# Symbs.net
KiCad netlist of a schematic drawn in Altium Designer
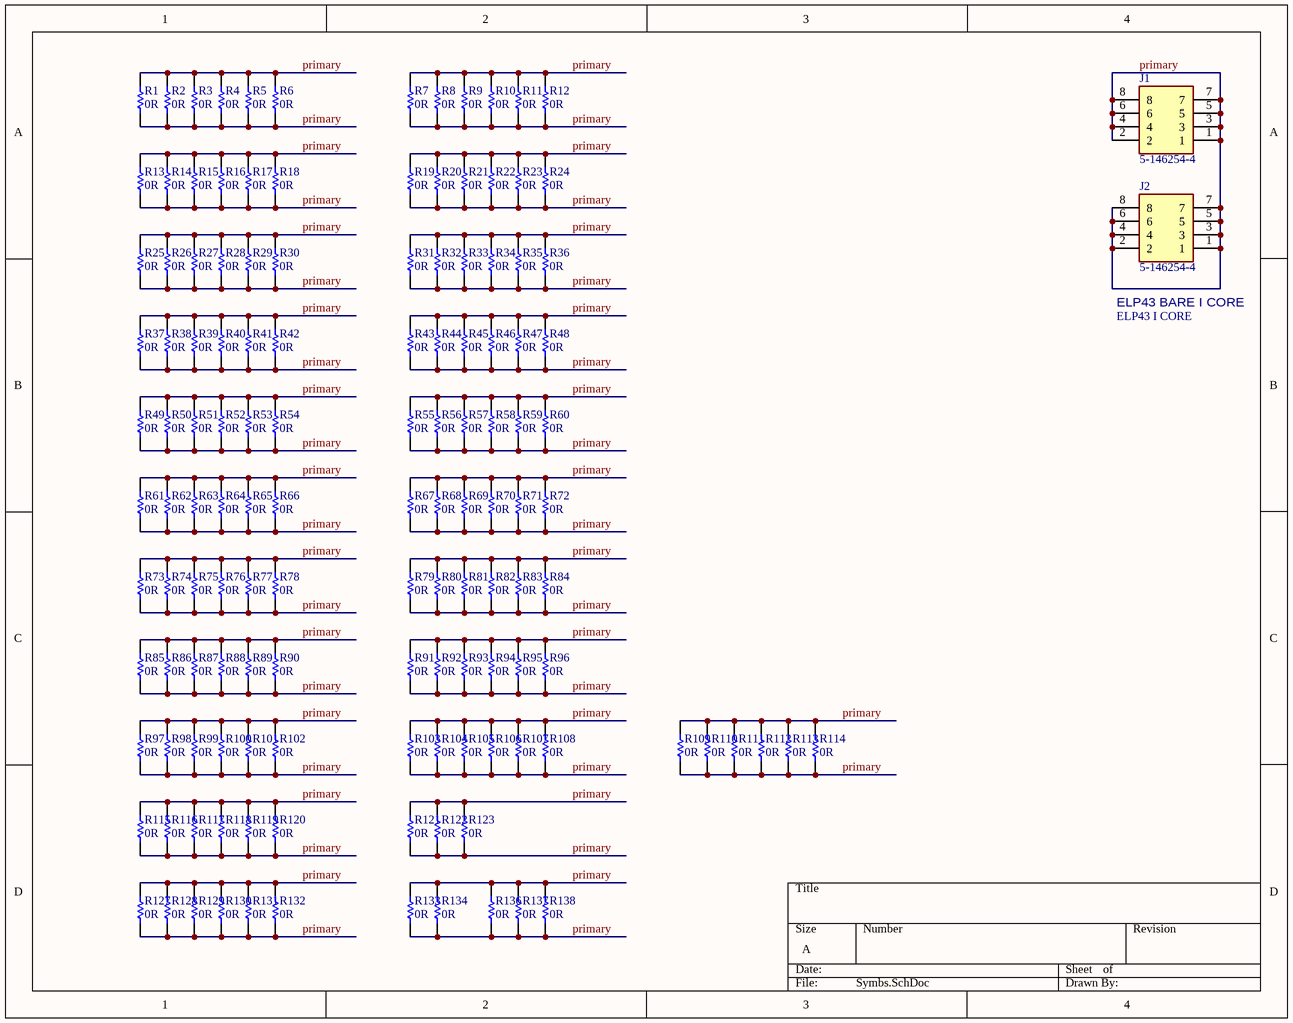
[diagram p0: Symbs.SchDoc]

(export (version "E")
  (design (tool "Eeschema 10.0.6"))
  (components
    (comp (ref "BODIES1")
      (value "ELP43 I CORE")
      (footprint "B66291G0000X187")
      (description "BODIES - ELP43 3D BODY CORE, I CORE")
      (libsource (lib "SamacSys") (part "ELP43 I CORE"))
    )
    (comp (ref "J1")
      (value "5-146254-4")
      (footprint "SamacSys:51462544")
      (description "Connector")
      (fields (field (name "MOUSER PART NUMBER") "571-5-146254-4"))
      (libsource (lib "*") (part "5-146254-4"))
    )
    (comp (ref "J2")
      (value "5-146254-4")
      (footprint "SamacSys:51462544")
      (description "Connector")
      (fields (field (name "MOUSER PART NUMBER") "571-5-146254-4"))
      (libsource (lib "*") (part "5-146254-4"))
    )
    (comp (ref "R1")
      (value "0R")
      (footprint "R_1206")
      (description "R - RESISTOR - SMD - 0R - 1% - 1206")
      (fields (field (name "LCSC PART #") "C17888") (field (name "Comment") "1206W4F0000T5E"))
      (libsource (lib "JLC_PCB") (part "1206W4F0000T5E"))
    )
    (comp (ref "R2")
      (value "0R")
      (footprint "R_1206")
      (description "R - RESISTOR - SMD - 0R - 1% - 1206")
      (fields (field (name "LCSC PART #") "C17888") (field (name "Comment") "1206W4F0000T5E"))
      (libsource (lib "JLC_PCB") (part "1206W4F0000T5E"))
    )
    (comp (ref "R3")
      (value "0R")
      (footprint "R_1206")
      (description "R - RESISTOR - SMD - 0R - 1% - 1206")
      (fields (field (name "LCSC PART #") "C17888") (field (name "Comment") "1206W4F0000T5E"))
      (libsource (lib "JLC_PCB") (part "1206W4F0000T5E"))
    )
    (comp (ref "R4")
      (value "0R")
      (footprint "R_1206")
      (description "R - RESISTOR - SMD - 0R - 1% - 1206")
      (fields (field (name "LCSC PART #") "C17888") (field (name "Comment") "1206W4F0000T5E"))
      (libsource (lib "JLC_PCB") (part "1206W4F0000T5E"))
    )
    (comp (ref "R5")
      (value "0R")
      (footprint "R_1206")
      (description "R - RESISTOR - SMD - 0R - 1% - 1206")
      (fields (field (name "LCSC PART #") "C17888") (field (name "Comment") "1206W4F0000T5E"))
      (libsource (lib "JLC_PCB") (part "1206W4F0000T5E"))
    )
    (comp (ref "R6")
      (value "0R")
      (footprint "R_1206")
      (description "R - RESISTOR - SMD - 0R - 1% - 1206")
      (fields (field (name "LCSC PART #") "C17888") (field (name "Comment") "1206W4F0000T5E"))
      (libsource (lib "JLC_PCB") (part "1206W4F0000T5E"))
    )
    (comp (ref "R7")
      (value "0R")
      (footprint "R_1206")
      (description "R - RESISTOR - SMD - 0R - 1% - 1206")
      (fields (field (name "LCSC PART #") "C17888") (field (name "Comment") "1206W4F0000T5E"))
      (libsource (lib "JLC_PCB") (part "1206W4F0000T5E"))
    )
    (comp (ref "R8")
      (value "0R")
      (footprint "R_1206")
      (description "R - RESISTOR - SMD - 0R - 1% - 1206")
      (fields (field (name "LCSC PART #") "C17888") (field (name "Comment") "1206W4F0000T5E"))
      (libsource (lib "JLC_PCB") (part "1206W4F0000T5E"))
    )
    (comp (ref "R9")
      (value "0R")
      (footprint "R_1206")
      (description "R - RESISTOR - SMD - 0R - 1% - 1206")
      (fields (field (name "LCSC PART #") "C17888") (field (name "Comment") "1206W4F0000T5E"))
      (libsource (lib "JLC_PCB") (part "1206W4F0000T5E"))
    )
    (comp (ref "R10")
      (value "0R")
      (footprint "R_1206")
      (description "R - RESISTOR - SMD - 0R - 1% - 1206")
      (fields (field (name "LCSC PART #") "C17888") (field (name "Comment") "1206W4F0000T5E"))
      (libsource (lib "JLC_PCB") (part "1206W4F0000T5E"))
    )
    (comp (ref "R11")
      (value "0R")
      (footprint "R_1206")
      (description "R - RESISTOR - SMD - 0R - 1% - 1206")
      (fields (field (name "LCSC PART #") "C17888") (field (name "Comment") "1206W4F0000T5E"))
      (libsource (lib "JLC_PCB") (part "1206W4F0000T5E"))
    )
    (comp (ref "R12")
      (value "0R")
      (footprint "R_1206")
      (description "R - RESISTOR - SMD - 0R - 1% - 1206")
      (fields (field (name "LCSC PART #") "C17888") (field (name "Comment") "1206W4F0000T5E"))
      (libsource (lib "JLC_PCB") (part "1206W4F0000T5E"))
    )
    (comp (ref "R13")
      (value "0R")
      (footprint "R_1206")
      (description "R - RESISTOR - SMD - 0R - 1% - 1206")
      (fields (field (name "LCSC PART #") "C17888") (field (name "Comment") "1206W4F0000T5E"))
      (libsource (lib "JLC_PCB") (part "1206W4F0000T5E"))
    )
    (comp (ref "R14")
      (value "0R")
      (footprint "R_1206")
      (description "R - RESISTOR - SMD - 0R - 1% - 1206")
      (fields (field (name "LCSC PART #") "C17888") (field (name "Comment") "1206W4F0000T5E"))
      (libsource (lib "JLC_PCB") (part "1206W4F0000T5E"))
    )
    (comp (ref "R15")
      (value "0R")
      (footprint "R_1206")
      (description "R - RESISTOR - SMD - 0R - 1% - 1206")
      (fields (field (name "LCSC PART #") "C17888") (field (name "Comment") "1206W4F0000T5E"))
      (libsource (lib "JLC_PCB") (part "1206W4F0000T5E"))
    )
    (comp (ref "R16")
      (value "0R")
      (footprint "R_1206")
      (description "R - RESISTOR - SMD - 0R - 1% - 1206")
      (fields (field (name "LCSC PART #") "C17888") (field (name "Comment") "1206W4F0000T5E"))
      (libsource (lib "JLC_PCB") (part "1206W4F0000T5E"))
    )
    (comp (ref "R17")
      (value "0R")
      (footprint "R_1206")
      (description "R - RESISTOR - SMD - 0R - 1% - 1206")
      (fields (field (name "LCSC PART #") "C17888") (field (name "Comment") "1206W4F0000T5E"))
      (libsource (lib "JLC_PCB") (part "1206W4F0000T5E"))
    )
    (comp (ref "R18")
      (value "0R")
      (footprint "R_1206")
      (description "R - RESISTOR - SMD - 0R - 1% - 1206")
      (fields (field (name "LCSC PART #") "C17888") (field (name "Comment") "1206W4F0000T5E"))
      (libsource (lib "JLC_PCB") (part "1206W4F0000T5E"))
    )
    (comp (ref "R19")
      (value "0R")
      (footprint "R_1206")
      (description "R - RESISTOR - SMD - 0R - 1% - 1206")
      (fields (field (name "LCSC PART #") "C17888") (field (name "Comment") "1206W4F0000T5E"))
      (libsource (lib "JLC_PCB") (part "1206W4F0000T5E"))
    )
    (comp (ref "R20")
      (value "0R")
      (footprint "R_1206")
      (description "R - RESISTOR - SMD - 0R - 1% - 1206")
      (fields (field (name "LCSC PART #") "C17888") (field (name "Comment") "1206W4F0000T5E"))
      (libsource (lib "JLC_PCB") (part "1206W4F0000T5E"))
    )
    (comp (ref "R21")
      (value "0R")
      (footprint "R_1206")
      (description "R - RESISTOR - SMD - 0R - 1% - 1206")
      (fields (field (name "LCSC PART #") "C17888") (field (name "Comment") "1206W4F0000T5E"))
      (libsource (lib "JLC_PCB") (part "1206W4F0000T5E"))
    )
    (comp (ref "R22")
      (value "0R")
      (footprint "R_1206")
      (description "R - RESISTOR - SMD - 0R - 1% - 1206")
      (fields (field (name "LCSC PART #") "C17888") (field (name "Comment") "1206W4F0000T5E"))
      (libsource (lib "JLC_PCB") (part "1206W4F0000T5E"))
    )
    (comp (ref "R23")
      (value "0R")
      (footprint "R_1206")
      (description "R - RESISTOR - SMD - 0R - 1% - 1206")
      (fields (field (name "LCSC PART #") "C17888") (field (name "Comment") "1206W4F0000T5E"))
      (libsource (lib "JLC_PCB") (part "1206W4F0000T5E"))
    )
    (comp (ref "R24")
      (value "0R")
      (footprint "R_1206")
      (description "R - RESISTOR - SMD - 0R - 1% - 1206")
      (fields (field (name "LCSC PART #") "C17888") (field (name "Comment") "1206W4F0000T5E"))
      (libsource (lib "JLC_PCB") (part "1206W4F0000T5E"))
    )
    (comp (ref "R25")
      (value "0R")
      (footprint "R_1206")
      (description "R - RESISTOR - SMD - 0R - 1% - 1206")
      (fields (field (name "LCSC PART #") "C17888") (field (name "Comment") "1206W4F0000T5E"))
      (libsource (lib "JLC_PCB") (part "1206W4F0000T5E"))
    )
    (comp (ref "R26")
      (value "0R")
      (footprint "R_1206")
      (description "R - RESISTOR - SMD - 0R - 1% - 1206")
      (fields (field (name "LCSC PART #") "C17888") (field (name "Comment") "1206W4F0000T5E"))
      (libsource (lib "JLC_PCB") (part "1206W4F0000T5E"))
    )
    (comp (ref "R27")
      (value "0R")
      (footprint "R_1206")
      (description "R - RESISTOR - SMD - 0R - 1% - 1206")
      (fields (field (name "LCSC PART #") "C17888") (field (name "Comment") "1206W4F0000T5E"))
      (libsource (lib "JLC_PCB") (part "1206W4F0000T5E"))
    )
    (comp (ref "R28")
      (value "0R")
      (footprint "R_1206")
      (description "R - RESISTOR - SMD - 0R - 1% - 1206")
      (fields (field (name "LCSC PART #") "C17888") (field (name "Comment") "1206W4F0000T5E"))
      (libsource (lib "JLC_PCB") (part "1206W4F0000T5E"))
    )
    (comp (ref "R29")
      (value "0R")
      (footprint "R_1206")
      (description "R - RESISTOR - SMD - 0R - 1% - 1206")
      (fields (field (name "LCSC PART #") "C17888") (field (name "Comment") "1206W4F0000T5E"))
      (libsource (lib "JLC_PCB") (part "1206W4F0000T5E"))
    )
    (comp (ref "R30")
      (value "0R")
      (footprint "R_1206")
      (description "R - RESISTOR - SMD - 0R - 1% - 1206")
      (fields (field (name "LCSC PART #") "C17888") (field (name "Comment") "1206W4F0000T5E"))
      (libsource (lib "JLC_PCB") (part "1206W4F0000T5E"))
    )
    (comp (ref "R31")
      (value "0R")
      (footprint "R_1206")
      (description "R - RESISTOR - SMD - 0R - 1% - 1206")
      (fields (field (name "LCSC PART #") "C17888") (field (name "Comment") "1206W4F0000T5E"))
      (libsource (lib "JLC_PCB") (part "1206W4F0000T5E"))
    )
    (comp (ref "R32")
      (value "0R")
      (footprint "R_1206")
      (description "R - RESISTOR - SMD - 0R - 1% - 1206")
      (fields (field (name "LCSC PART #") "C17888") (field (name "Comment") "1206W4F0000T5E"))
      (libsource (lib "JLC_PCB") (part "1206W4F0000T5E"))
    )
    (comp (ref "R33")
      (value "0R")
      (footprint "R_1206")
      (description "R - RESISTOR - SMD - 0R - 1% - 1206")
      (fields (field (name "LCSC PART #") "C17888") (field (name "Comment") "1206W4F0000T5E"))
      (libsource (lib "JLC_PCB") (part "1206W4F0000T5E"))
    )
    (comp (ref "R34")
      (value "0R")
      (footprint "R_1206")
      (description "R - RESISTOR - SMD - 0R - 1% - 1206")
      (fields (field (name "LCSC PART #") "C17888") (field (name "Comment") "1206W4F0000T5E"))
      (libsource (lib "JLC_PCB") (part "1206W4F0000T5E"))
    )
    (comp (ref "R35")
      (value "0R")
      (footprint "R_1206")
      (description "R - RESISTOR - SMD - 0R - 1% - 1206")
      (fields (field (name "LCSC PART #") "C17888") (field (name "Comment") "1206W4F0000T5E"))
      (libsource (lib "JLC_PCB") (part "1206W4F0000T5E"))
    )
    (comp (ref "R36")
      (value "0R")
      (footprint "R_1206")
      (description "R - RESISTOR - SMD - 0R - 1% - 1206")
      (fields (field (name "LCSC PART #") "C17888") (field (name "Comment") "1206W4F0000T5E"))
      (libsource (lib "JLC_PCB") (part "1206W4F0000T5E"))
    )
    (comp (ref "R37")
      (value "0R")
      (footprint "R_1206")
      (description "R - RESISTOR - SMD - 0R - 1% - 1206")
      (fields (field (name "LCSC PART #") "C17888") (field (name "Comment") "1206W4F0000T5E"))
      (libsource (lib "JLC_PCB") (part "1206W4F0000T5E"))
    )
    (comp (ref "R38")
      (value "0R")
      (footprint "R_1206")
      (description "R - RESISTOR - SMD - 0R - 1% - 1206")
      (fields (field (name "LCSC PART #") "C17888") (field (name "Comment") "1206W4F0000T5E"))
      (libsource (lib "JLC_PCB") (part "1206W4F0000T5E"))
    )
    (comp (ref "R39")
      (value "0R")
      (footprint "R_1206")
      (description "R - RESISTOR - SMD - 0R - 1% - 1206")
      (fields (field (name "LCSC PART #") "C17888") (field (name "Comment") "1206W4F0000T5E"))
      (libsource (lib "JLC_PCB") (part "1206W4F0000T5E"))
    )
    (comp (ref "R40")
      (value "0R")
      (footprint "R_1206")
      (description "R - RESISTOR - SMD - 0R - 1% - 1206")
      (fields (field (name "LCSC PART #") "C17888") (field (name "Comment") "1206W4F0000T5E"))
      (libsource (lib "JLC_PCB") (part "1206W4F0000T5E"))
    )
    (comp (ref "R41")
      (value "0R")
      (footprint "R_1206")
      (description "R - RESISTOR - SMD - 0R - 1% - 1206")
      (fields (field (name "LCSC PART #") "C17888") (field (name "Comment") "1206W4F0000T5E"))
      (libsource (lib "JLC_PCB") (part "1206W4F0000T5E"))
    )
    (comp (ref "R42")
      (value "0R")
      (footprint "R_1206")
      (description "R - RESISTOR - SMD - 0R - 1% - 1206")
      (fields (field (name "LCSC PART #") "C17888") (field (name "Comment") "1206W4F0000T5E"))
      (libsource (lib "JLC_PCB") (part "1206W4F0000T5E"))
    )
    (comp (ref "R43")
      (value "0R")
      (footprint "R_1206")
      (description "R - RESISTOR - SMD - 0R - 1% - 1206")
      (fields (field (name "LCSC PART #") "C17888") (field (name "Comment") "1206W4F0000T5E"))
      (libsource (lib "JLC_PCB") (part "1206W4F0000T5E"))
    )
    (comp (ref "R44")
      (value "0R")
      (footprint "R_1206")
      (description "R - RESISTOR - SMD - 0R - 1% - 1206")
      (fields (field (name "LCSC PART #") "C17888") (field (name "Comment") "1206W4F0000T5E"))
      (libsource (lib "JLC_PCB") (part "1206W4F0000T5E"))
    )
    (comp (ref "R45")
      (value "0R")
      (footprint "R_1206")
      (description "R - RESISTOR - SMD - 0R - 1% - 1206")
      (fields (field (name "LCSC PART #") "C17888") (field (name "Comment") "1206W4F0000T5E"))
      (libsource (lib "JLC_PCB") (part "1206W4F0000T5E"))
    )
    (comp (ref "R46")
      (value "0R")
      (footprint "R_1206")
      (description "R - RESISTOR - SMD - 0R - 1% - 1206")
      (fields (field (name "LCSC PART #") "C17888") (field (name "Comment") "1206W4F0000T5E"))
      (libsource (lib "JLC_PCB") (part "1206W4F0000T5E"))
    )
    (comp (ref "R47")
      (value "0R")
      (footprint "R_1206")
      (description "R - RESISTOR - SMD - 0R - 1% - 1206")
      (fields (field (name "LCSC PART #") "C17888") (field (name "Comment") "1206W4F0000T5E"))
      (libsource (lib "JLC_PCB") (part "1206W4F0000T5E"))
    )
    (comp (ref "R48")
      (value "0R")
      (footprint "R_1206")
      (description "R - RESISTOR - SMD - 0R - 1% - 1206")
      (fields (field (name "LCSC PART #") "C17888") (field (name "Comment") "1206W4F0000T5E"))
      (libsource (lib "JLC_PCB") (part "1206W4F0000T5E"))
    )
    (comp (ref "R49")
      (value "0R")
      (footprint "R_1206")
      (description "R - RESISTOR - SMD - 0R - 1% - 1206")
      (fields (field (name "LCSC PART #") "C17888") (field (name "Comment") "1206W4F0000T5E"))
      (libsource (lib "JLC_PCB") (part "1206W4F0000T5E"))
    )
    (comp (ref "R50")
      (value "0R")
      (footprint "R_1206")
      (description "R - RESISTOR - SMD - 0R - 1% - 1206")
      (fields (field (name "LCSC PART #") "C17888") (field (name "Comment") "1206W4F0000T5E"))
      (libsource (lib "JLC_PCB") (part "1206W4F0000T5E"))
    )
    (comp (ref "R51")
      (value "0R")
      (footprint "R_1206")
      (description "R - RESISTOR - SMD - 0R - 1% - 1206")
      (fields (field (name "LCSC PART #") "C17888") (field (name "Comment") "1206W4F0000T5E"))
      (libsource (lib "JLC_PCB") (part "1206W4F0000T5E"))
    )
    (comp (ref "R52")
      (value "0R")
      (footprint "R_1206")
      (description "R - RESISTOR - SMD - 0R - 1% - 1206")
      (fields (field (name "LCSC PART #") "C17888") (field (name "Comment") "1206W4F0000T5E"))
      (libsource (lib "JLC_PCB") (part "1206W4F0000T5E"))
    )
    (comp (ref "R53")
      (value "0R")
      (footprint "R_1206")
      (description "R - RESISTOR - SMD - 0R - 1% - 1206")
      (fields (field (name "LCSC PART #") "C17888") (field (name "Comment") "1206W4F0000T5E"))
      (libsource (lib "JLC_PCB") (part "1206W4F0000T5E"))
    )
    (comp (ref "R54")
      (value "0R")
      (footprint "R_1206")
      (description "R - RESISTOR - SMD - 0R - 1% - 1206")
      (fields (field (name "LCSC PART #") "C17888") (field (name "Comment") "1206W4F0000T5E"))
      (libsource (lib "JLC_PCB") (part "1206W4F0000T5E"))
    )
    (comp (ref "R55")
      (value "0R")
      (footprint "R_1206")
      (description "R - RESISTOR - SMD - 0R - 1% - 1206")
      (fields (field (name "LCSC PART #") "C17888") (field (name "Comment") "1206W4F0000T5E"))
      (libsource (lib "JLC_PCB") (part "1206W4F0000T5E"))
    )
    (comp (ref "R56")
      (value "0R")
      (footprint "R_1206")
      (description "R - RESISTOR - SMD - 0R - 1% - 1206")
      (fields (field (name "LCSC PART #") "C17888") (field (name "Comment") "1206W4F0000T5E"))
      (libsource (lib "JLC_PCB") (part "1206W4F0000T5E"))
    )
    (comp (ref "R57")
      (value "0R")
      (footprint "R_1206")
      (description "R - RESISTOR - SMD - 0R - 1% - 1206")
      (fields (field (name "LCSC PART #") "C17888") (field (name "Comment") "1206W4F0000T5E"))
      (libsource (lib "JLC_PCB") (part "1206W4F0000T5E"))
    )
    (comp (ref "R58")
      (value "0R")
      (footprint "R_1206")
      (description "R - RESISTOR - SMD - 0R - 1% - 1206")
      (fields (field (name "LCSC PART #") "C17888") (field (name "Comment") "1206W4F0000T5E"))
      (libsource (lib "JLC_PCB") (part "1206W4F0000T5E"))
    )
    (comp (ref "R59")
      (value "0R")
      (footprint "R_1206")
      (description "R - RESISTOR - SMD - 0R - 1% - 1206")
      (fields (field (name "LCSC PART #") "C17888") (field (name "Comment") "1206W4F0000T5E"))
      (libsource (lib "JLC_PCB") (part "1206W4F0000T5E"))
    )
    (comp (ref "R60")
      (value "0R")
      (footprint "R_1206")
      (description "R - RESISTOR - SMD - 0R - 1% - 1206")
      (fields (field (name "LCSC PART #") "C17888") (field (name "Comment") "1206W4F0000T5E"))
      (libsource (lib "JLC_PCB") (part "1206W4F0000T5E"))
    )
    (comp (ref "R61")
      (value "0R")
      (footprint "R_1206")
      (description "R - RESISTOR - SMD - 0R - 1% - 1206")
      (fields (field (name "LCSC PART #") "C17888") (field (name "Comment") "1206W4F0000T5E"))
      (libsource (lib "JLC_PCB") (part "1206W4F0000T5E"))
    )
    (comp (ref "R62")
      (value "0R")
      (footprint "R_1206")
      (description "R - RESISTOR - SMD - 0R - 1% - 1206")
      (fields (field (name "LCSC PART #") "C17888") (field (name "Comment") "1206W4F0000T5E"))
      (libsource (lib "JLC_PCB") (part "1206W4F0000T5E"))
    )
    (comp (ref "R63")
      (value "0R")
      (footprint "R_1206")
      (description "R - RESISTOR - SMD - 0R - 1% - 1206")
      (fields (field (name "LCSC PART #") "C17888") (field (name "Comment") "1206W4F0000T5E"))
      (libsource (lib "JLC_PCB") (part "1206W4F0000T5E"))
    )
    (comp (ref "R64")
      (value "0R")
      (footprint "R_1206")
      (description "R - RESISTOR - SMD - 0R - 1% - 1206")
      (fields (field (name "LCSC PART #") "C17888") (field (name "Comment") "1206W4F0000T5E"))
      (libsource (lib "JLC_PCB") (part "1206W4F0000T5E"))
    )
    (comp (ref "R65")
      (value "0R")
      (footprint "R_1206")
      (description "R - RESISTOR - SMD - 0R - 1% - 1206")
      (fields (field (name "LCSC PART #") "C17888") (field (name "Comment") "1206W4F0000T5E"))
      (libsource (lib "JLC_PCB") (part "1206W4F0000T5E"))
    )
    (comp (ref "R66")
      (value "0R")
      (footprint "R_1206")
      (description "R - RESISTOR - SMD - 0R - 1% - 1206")
      (fields (field (name "LCSC PART #") "C17888") (field (name "Comment") "1206W4F0000T5E"))
      (libsource (lib "JLC_PCB") (part "1206W4F0000T5E"))
    )
    (comp (ref "R67")
      (value "0R")
      (footprint "R_1206")
      (description "R - RESISTOR - SMD - 0R - 1% - 1206")
      (fields (field (name "LCSC PART #") "C17888") (field (name "Comment") "1206W4F0000T5E"))
      (libsource (lib "JLC_PCB") (part "1206W4F0000T5E"))
    )
    (comp (ref "R68")
      (value "0R")
      (footprint "R_1206")
      (description "R - RESISTOR - SMD - 0R - 1% - 1206")
      (fields (field (name "LCSC PART #") "C17888") (field (name "Comment") "1206W4F0000T5E"))
      (libsource (lib "JLC_PCB") (part "1206W4F0000T5E"))
    )
    (comp (ref "R69")
      (value "0R")
      (footprint "R_1206")
      (description "R - RESISTOR - SMD - 0R - 1% - 1206")
      (fields (field (name "LCSC PART #") "C17888") (field (name "Comment") "1206W4F0000T5E"))
      (libsource (lib "JLC_PCB") (part "1206W4F0000T5E"))
    )
    (comp (ref "R70")
      (value "0R")
      (footprint "R_1206")
      (description "R - RESISTOR - SMD - 0R - 1% - 1206")
      (fields (field (name "LCSC PART #") "C17888") (field (name "Comment") "1206W4F0000T5E"))
      (libsource (lib "JLC_PCB") (part "1206W4F0000T5E"))
    )
    (comp (ref "R71")
      (value "0R")
      (footprint "R_1206")
      (description "R - RESISTOR - SMD - 0R - 1% - 1206")
      (fields (field (name "LCSC PART #") "C17888") (field (name "Comment") "1206W4F0000T5E"))
      (libsource (lib "JLC_PCB") (part "1206W4F0000T5E"))
    )
    (comp (ref "R72")
      (value "0R")
      (footprint "R_1206")
      (description "R - RESISTOR - SMD - 0R - 1% - 1206")
      (fields (field (name "LCSC PART #") "C17888") (field (name "Comment") "1206W4F0000T5E"))
      (libsource (lib "JLC_PCB") (part "1206W4F0000T5E"))
    )
    (comp (ref "R73")
      (value "0R")
      (footprint "R_1206")
      (description "R - RESISTOR - SMD - 0R - 1% - 1206")
      (fields (field (name "LCSC PART #") "C17888") (field (name "Comment") "1206W4F0000T5E"))
      (libsource (lib "JLC_PCB") (part "1206W4F0000T5E"))
    )
    (comp (ref "R74")
      (value "0R")
      (footprint "R_1206")
      (description "R - RESISTOR - SMD - 0R - 1% - 1206")
      (fields (field (name "LCSC PART #") "C17888") (field (name "Comment") "1206W4F0000T5E"))
      (libsource (lib "JLC_PCB") (part "1206W4F0000T5E"))
    )
    (comp (ref "R75")
      (value "0R")
      (footprint "R_1206")
      (description "R - RESISTOR - SMD - 0R - 1% - 1206")
      (fields (field (name "LCSC PART #") "C17888") (field (name "Comment") "1206W4F0000T5E"))
      (libsource (lib "JLC_PCB") (part "1206W4F0000T5E"))
    )
    (comp (ref "R76")
      (value "0R")
      (footprint "R_1206")
      (description "R - RESISTOR - SMD - 0R - 1% - 1206")
      (fields (field (name "LCSC PART #") "C17888") (field (name "Comment") "1206W4F0000T5E"))
      (libsource (lib "JLC_PCB") (part "1206W4F0000T5E"))
    )
    (comp (ref "R77")
      (value "0R")
      (footprint "R_1206")
      (description "R - RESISTOR - SMD - 0R - 1% - 1206")
      (fields (field (name "LCSC PART #") "C17888") (field (name "Comment") "1206W4F0000T5E"))
      (libsource (lib "JLC_PCB") (part "1206W4F0000T5E"))
    )
    (comp (ref "R78")
      (value "0R")
      (footprint "R_1206")
      (description "R - RESISTOR - SMD - 0R - 1% - 1206")
      (fields (field (name "LCSC PART #") "C17888") (field (name "Comment") "1206W4F0000T5E"))
      (libsource (lib "JLC_PCB") (part "1206W4F0000T5E"))
    )
    (comp (ref "R79")
      (value "0R")
      (footprint "R_1206")
      (description "R - RESISTOR - SMD - 0R - 1% - 1206")
      (fields (field (name "LCSC PART #") "C17888") (field (name "Comment") "1206W4F0000T5E"))
      (libsource (lib "JLC_PCB") (part "1206W4F0000T5E"))
    )
    (comp (ref "R80")
      (value "0R")
      (footprint "R_1206")
      (description "R - RESISTOR - SMD - 0R - 1% - 1206")
      (fields (field (name "LCSC PART #") "C17888") (field (name "Comment") "1206W4F0000T5E"))
      (libsource (lib "JLC_PCB") (part "1206W4F0000T5E"))
    )
    (comp (ref "R81")
      (value "0R")
      (footprint "R_1206")
      (description "R - RESISTOR - SMD - 0R - 1% - 1206")
      (fields (field (name "LCSC PART #") "C17888") (field (name "Comment") "1206W4F0000T5E"))
      (libsource (lib "JLC_PCB") (part "1206W4F0000T5E"))
    )
    (comp (ref "R82")
      (value "0R")
      (footprint "R_1206")
      (description "R - RESISTOR - SMD - 0R - 1% - 1206")
      (fields (field (name "LCSC PART #") "C17888") (field (name "Comment") "1206W4F0000T5E"))
      (libsource (lib "JLC_PCB") (part "1206W4F0000T5E"))
    )
    (comp (ref "R83")
      (value "0R")
      (footprint "R_1206")
      (description "R - RESISTOR - SMD - 0R - 1% - 1206")
      (fields (field (name "LCSC PART #") "C17888") (field (name "Comment") "1206W4F0000T5E"))
      (libsource (lib "JLC_PCB") (part "1206W4F0000T5E"))
    )
    (comp (ref "R84")
      (value "0R")
      (footprint "R_1206")
      (description "R - RESISTOR - SMD - 0R - 1% - 1206")
      (fields (field (name "LCSC PART #") "C17888") (field (name "Comment") "1206W4F0000T5E"))
      (libsource (lib "JLC_PCB") (part "1206W4F0000T5E"))
    )
    (comp (ref "R85")
      (value "0R")
      (footprint "R_1206")
      (description "R - RESISTOR - SMD - 0R - 1% - 1206")
      (fields (field (name "LCSC PART #") "C17888") (field (name "Comment") "1206W4F0000T5E"))
      (libsource (lib "JLC_PCB") (part "1206W4F0000T5E"))
    )
    (comp (ref "R86")
      (value "0R")
      (footprint "R_1206")
      (description "R - RESISTOR - SMD - 0R - 1% - 1206")
      (fields (field (name "LCSC PART #") "C17888") (field (name "Comment") "1206W4F0000T5E"))
      (libsource (lib "JLC_PCB") (part "1206W4F0000T5E"))
    )
    (comp (ref "R87")
      (value "0R")
      (footprint "R_1206")
      (description "R - RESISTOR - SMD - 0R - 1% - 1206")
      (fields (field (name "LCSC PART #") "C17888") (field (name "Comment") "1206W4F0000T5E"))
      (libsource (lib "JLC_PCB") (part "1206W4F0000T5E"))
    )
    (comp (ref "R88")
      (value "0R")
      (footprint "R_1206")
      (description "R - RESISTOR - SMD - 0R - 1% - 1206")
      (fields (field (name "LCSC PART #") "C17888") (field (name "Comment") "1206W4F0000T5E"))
      (libsource (lib "JLC_PCB") (part "1206W4F0000T5E"))
    )
    (comp (ref "R89")
      (value "0R")
      (footprint "R_1206")
      (description "R - RESISTOR - SMD - 0R - 1% - 1206")
      (fields (field (name "LCSC PART #") "C17888") (field (name "Comment") "1206W4F0000T5E"))
      (libsource (lib "JLC_PCB") (part "1206W4F0000T5E"))
    )
    (comp (ref "R90")
      (value "0R")
      (footprint "R_1206")
      (description "R - RESISTOR - SMD - 0R - 1% - 1206")
      (fields (field (name "LCSC PART #") "C17888") (field (name "Comment") "1206W4F0000T5E"))
      (libsource (lib "JLC_PCB") (part "1206W4F0000T5E"))
    )
    (comp (ref "R91")
      (value "0R")
      (footprint "R_1206")
      (description "R - RESISTOR - SMD - 0R - 1% - 1206")
      (fields (field (name "LCSC PART #") "C17888") (field (name "Comment") "1206W4F0000T5E"))
      (libsource (lib "JLC_PCB") (part "1206W4F0000T5E"))
    )
    (comp (ref "R92")
      (value "0R")
      (footprint "R_1206")
      (description "R - RESISTOR - SMD - 0R - 1% - 1206")
      (fields (field (name "LCSC PART #") "C17888") (field (name "Comment") "1206W4F0000T5E"))
      (libsource (lib "JLC_PCB") (part "1206W4F0000T5E"))
    )
    (comp (ref "R93")
      (value "0R")
      (footprint "R_1206")
      (description "R - RESISTOR - SMD - 0R - 1% - 1206")
      (fields (field (name "LCSC PART #") "C17888") (field (name "Comment") "1206W4F0000T5E"))
      (libsource (lib "JLC_PCB") (part "1206W4F0000T5E"))
    )
    (comp (ref "R94")
      (value "0R")
      (footprint "R_1206")
      (description "R - RESISTOR - SMD - 0R - 1% - 1206")
      (fields (field (name "LCSC PART #") "C17888") (field (name "Comment") "1206W4F0000T5E"))
      (libsource (lib "JLC_PCB") (part "1206W4F0000T5E"))
    )
    (comp (ref "R95")
      (value "0R")
      (footprint "R_1206")
      (description "R - RESISTOR - SMD - 0R - 1% - 1206")
      (fields (field (name "LCSC PART #") "C17888") (field (name "Comment") "1206W4F0000T5E"))
      (libsource (lib "JLC_PCB") (part "1206W4F0000T5E"))
    )
    (comp (ref "R96")
      (value "0R")
      (footprint "R_1206")
      (description "R - RESISTOR - SMD - 0R - 1% - 1206")
      (fields (field (name "LCSC PART #") "C17888") (field (name "Comment") "1206W4F0000T5E"))
      (libsource (lib "JLC_PCB") (part "1206W4F0000T5E"))
    )
    (comp (ref "R97")
      (value "0R")
      (footprint "R_1206")
      (description "R - RESISTOR - SMD - 0R - 1% - 1206")
      (fields (field (name "LCSC PART #") "C17888") (field (name "Comment") "1206W4F0000T5E"))
      (libsource (lib "JLC_PCB") (part "1206W4F0000T5E"))
    )
    (comp (ref "R98")
      (value "0R")
      (footprint "R_1206")
      (description "R - RESISTOR - SMD - 0R - 1% - 1206")
      (fields (field (name "LCSC PART #") "C17888") (field (name "Comment") "1206W4F0000T5E"))
      (libsource (lib "JLC_PCB") (part "1206W4F0000T5E"))
    )
    (comp (ref "R99")
      (value "0R")
      (footprint "R_1206")
      (description "R - RESISTOR - SMD - 0R - 1% - 1206")
      (fields (field (name "LCSC PART #") "C17888") (field (name "Comment") "1206W4F0000T5E"))
      (libsource (lib "JLC_PCB") (part "1206W4F0000T5E"))
    )
    (comp (ref "R100")
      (value "0R")
      (footprint "R_1206")
      (description "R - RESISTOR - SMD - 0R - 1% - 1206")
      (fields (field (name "LCSC PART #") "C17888") (field (name "Comment") "1206W4F0000T5E"))
      (libsource (lib "JLC_PCB") (part "1206W4F0000T5E"))
    )
    (comp (ref "R101")
      (value "0R")
      (footprint "R_1206")
      (description "R - RESISTOR - SMD - 0R - 1% - 1206")
      (fields (field (name "LCSC PART #") "C17888") (field (name "Comment") "1206W4F0000T5E"))
      (libsource (lib "JLC_PCB") (part "1206W4F0000T5E"))
    )
    (comp (ref "R102")
      (value "0R")
      (footprint "R_1206")
      (description "R - RESISTOR - SMD - 0R - 1% - 1206")
      (fields (field (name "LCSC PART #") "C17888") (field (name "Comment") "1206W4F0000T5E"))
      (libsource (lib "JLC_PCB") (part "1206W4F0000T5E"))
    )
    (comp (ref "R103")
      (value "0R")
      (footprint "R_1206")
      (description "R - RESISTOR - SMD - 0R - 1% - 1206")
      (fields (field (name "LCSC PART #") "C17888") (field (name "Comment") "1206W4F0000T5E"))
      (libsource (lib "JLC_PCB") (part "1206W4F0000T5E"))
    )
    (comp (ref "R104")
      (value "0R")
      (footprint "R_1206")
      (description "R - RESISTOR - SMD - 0R - 1% - 1206")
      (fields (field (name "LCSC PART #") "C17888") (field (name "Comment") "1206W4F0000T5E"))
      (libsource (lib "JLC_PCB") (part "1206W4F0000T5E"))
    )
    (comp (ref "R105")
      (value "0R")
      (footprint "R_1206")
      (description "R - RESISTOR - SMD - 0R - 1% - 1206")
      (fields (field (name "LCSC PART #") "C17888") (field (name "Comment") "1206W4F0000T5E"))
      (libsource (lib "JLC_PCB") (part "1206W4F0000T5E"))
    )
    (comp (ref "R106")
      (value "0R")
      (footprint "R_1206")
      (description "R - RESISTOR - SMD - 0R - 1% - 1206")
      (fields (field (name "LCSC PART #") "C17888") (field (name "Comment") "1206W4F0000T5E"))
      (libsource (lib "JLC_PCB") (part "1206W4F0000T5E"))
    )
    (comp (ref "R107")
      (value "0R")
      (footprint "R_1206")
      (description "R - RESISTOR - SMD - 0R - 1% - 1206")
      (fields (field (name "LCSC PART #") "C17888") (field (name "Comment") "1206W4F0000T5E"))
      (libsource (lib "JLC_PCB") (part "1206W4F0000T5E"))
    )
    (comp (ref "R108")
      (value "0R")
      (footprint "R_1206")
      (description "R - RESISTOR - SMD - 0R - 1% - 1206")
      (fields (field (name "LCSC PART #") "C17888") (field (name "Comment") "1206W4F0000T5E"))
      (libsource (lib "JLC_PCB") (part "1206W4F0000T5E"))
    )
    (comp (ref "R109")
      (value "0R")
      (footprint "R_1206")
      (description "R - RESISTOR - SMD - 0R - 1% - 1206")
      (fields (field (name "LCSC PART #") "C17888") (field (name "Comment") "1206W4F0000T5E"))
      (libsource (lib "JLC_PCB") (part "1206W4F0000T5E"))
    )
    (comp (ref "R110")
      (value "0R")
      (footprint "R_1206")
      (description "R - RESISTOR - SMD - 0R - 1% - 1206")
      (fields (field (name "LCSC PART #") "C17888") (field (name "Comment") "1206W4F0000T5E"))
      (libsource (lib "JLC_PCB") (part "1206W4F0000T5E"))
    )
    (comp (ref "R111")
      (value "0R")
      (footprint "R_1206")
      (description "R - RESISTOR - SMD - 0R - 1% - 1206")
      (fields (field (name "LCSC PART #") "C17888") (field (name "Comment") "1206W4F0000T5E"))
      (libsource (lib "JLC_PCB") (part "1206W4F0000T5E"))
    )
    (comp (ref "R112")
      (value "0R")
      (footprint "R_1206")
      (description "R - RESISTOR - SMD - 0R - 1% - 1206")
      (fields (field (name "LCSC PART #") "C17888") (field (name "Comment") "1206W4F0000T5E"))
      (libsource (lib "JLC_PCB") (part "1206W4F0000T5E"))
    )
    (comp (ref "R113")
      (value "0R")
      (footprint "R_1206")
      (description "R - RESISTOR - SMD - 0R - 1% - 1206")
      (fields (field (name "LCSC PART #") "C17888") (field (name "Comment") "1206W4F0000T5E"))
      (libsource (lib "JLC_PCB") (part "1206W4F0000T5E"))
    )
    (comp (ref "R114")
      (value "0R")
      (footprint "R_1206")
      (description "R - RESISTOR - SMD - 0R - 1% - 1206")
      (fields (field (name "LCSC PART #") "C17888") (field (name "Comment") "1206W4F0000T5E"))
      (libsource (lib "JLC_PCB") (part "1206W4F0000T5E"))
    )
    (comp (ref "R115")
      (value "0R")
      (footprint "R_1206")
      (description "R - RESISTOR - SMD - 0R - 1% - 1206")
      (fields (field (name "LCSC PART #") "C17888") (field (name "Comment") "1206W4F0000T5E"))
      (libsource (lib "JLC_PCB") (part "1206W4F0000T5E"))
    )
    (comp (ref "R116")
      (value "0R")
      (footprint "R_1206")
      (description "R - RESISTOR - SMD - 0R - 1% - 1206")
      (fields (field (name "LCSC PART #") "C17888") (field (name "Comment") "1206W4F0000T5E"))
      (libsource (lib "JLC_PCB") (part "1206W4F0000T5E"))
    )
    (comp (ref "R117")
      (value "0R")
      (footprint "R_1206")
      (description "R - RESISTOR - SMD - 0R - 1% - 1206")
      (fields (field (name "LCSC PART #") "C17888") (field (name "Comment") "1206W4F0000T5E"))
      (libsource (lib "JLC_PCB") (part "1206W4F0000T5E"))
    )
    (comp (ref "R118")
      (value "0R")
      (footprint "R_1206")
      (description "R - RESISTOR - SMD - 0R - 1% - 1206")
      (fields (field (name "LCSC PART #") "C17888") (field (name "Comment") "1206W4F0000T5E"))
      (libsource (lib "JLC_PCB") (part "1206W4F0000T5E"))
    )
    (comp (ref "R119")
      (value "0R")
      (footprint "R_1206")
      (description "R - RESISTOR - SMD - 0R - 1% - 1206")
      (fields (field (name "LCSC PART #") "C17888") (field (name "Comment") "1206W4F0000T5E"))
      (libsource (lib "JLC_PCB") (part "1206W4F0000T5E"))
    )
    (comp (ref "R120")
      (value "0R")
      (footprint "R_1206")
      (description "R - RESISTOR - SMD - 0R - 1% - 1206")
      (fields (field (name "LCSC PART #") "C17888") (field (name "Comment") "1206W4F0000T5E"))
      (libsource (lib "JLC_PCB") (part "1206W4F0000T5E"))
    )
    (comp (ref "R121")
      (value "0R")
      (footprint "R_1206")
      (description "R - RESISTOR - SMD - 0R - 1% - 1206")
      (fields (field (name "LCSC PART #") "C17888") (field (name "Comment") "1206W4F0000T5E"))
      (libsource (lib "JLC_PCB") (part "1206W4F0000T5E"))
    )
    (comp (ref "R122")
      (value "0R")
      (footprint "R_1206")
      (description "R - RESISTOR - SMD - 0R - 1% - 1206")
      (fields (field (name "LCSC PART #") "C17888") (field (name "Comment") "1206W4F0000T5E"))
      (libsource (lib "JLC_PCB") (part "1206W4F0000T5E"))
    )
    (comp (ref "R123")
      (value "0R")
      (footprint "R_1206")
      (description "R - RESISTOR - SMD - 0R - 1% - 1206")
      (fields (field (name "LCSC PART #") "C17888") (field (name "Comment") "1206W4F0000T5E"))
      (libsource (lib "JLC_PCB") (part "1206W4F0000T5E"))
    )
    (comp (ref "R127")
      (value "0R")
      (footprint "R_1206")
      (description "R - RESISTOR - SMD - 0R - 1% - 1206")
      (fields (field (name "LCSC PART #") "C17888") (field (name "Comment") "1206W4F0000T5E"))
      (libsource (lib "JLC_PCB") (part "1206W4F0000T5E"))
    )
    (comp (ref "R128")
      (value "0R")
      (footprint "R_1206")
      (description "R - RESISTOR - SMD - 0R - 1% - 1206")
      (fields (field (name "LCSC PART #") "C17888") (field (name "Comment") "1206W4F0000T5E"))
      (libsource (lib "JLC_PCB") (part "1206W4F0000T5E"))
    )
    (comp (ref "R129")
      (value "0R")
      (footprint "R_1206")
      (description "R - RESISTOR - SMD - 0R - 1% - 1206")
      (fields (field (name "LCSC PART #") "C17888") (field (name "Comment") "1206W4F0000T5E"))
      (libsource (lib "JLC_PCB") (part "1206W4F0000T5E"))
    )
    (comp (ref "R130")
      (value "0R")
      (footprint "R_1206")
      (description "R - RESISTOR - SMD - 0R - 1% - 1206")
      (fields (field (name "LCSC PART #") "C17888") (field (name "Comment") "1206W4F0000T5E"))
      (libsource (lib "JLC_PCB") (part "1206W4F0000T5E"))
    )
    (comp (ref "R131")
      (value "0R")
      (footprint "R_1206")
      (description "R - RESISTOR - SMD - 0R - 1% - 1206")
      (fields (field (name "LCSC PART #") "C17888") (field (name "Comment") "1206W4F0000T5E"))
      (libsource (lib "JLC_PCB") (part "1206W4F0000T5E"))
    )
    (comp (ref "R132")
      (value "0R")
      (footprint "R_1206")
      (description "R - RESISTOR - SMD - 0R - 1% - 1206")
      (fields (field (name "LCSC PART #") "C17888") (field (name "Comment") "1206W4F0000T5E"))
      (libsource (lib "JLC_PCB") (part "1206W4F0000T5E"))
    )
    (comp (ref "R133")
      (value "0R")
      (footprint "R_1206")
      (description "R - RESISTOR - SMD - 0R - 1% - 1206")
      (fields (field (name "LCSC PART #") "C17888") (field (name "Comment") "1206W4F0000T5E"))
      (libsource (lib "JLC_PCB") (part "1206W4F0000T5E"))
    )
    (comp (ref "R134")
      (value "0R")
      (footprint "R_1206")
      (description "R - RESISTOR - SMD - 0R - 1% - 1206")
      (fields (field (name "LCSC PART #") "C17888") (field (name "Comment") "1206W4F0000T5E"))
      (libsource (lib "JLC_PCB") (part "1206W4F0000T5E"))
    )
    (comp (ref "R136")
      (value "0R")
      (footprint "R_1206")
      (description "R - RESISTOR - SMD - 0R - 1% - 1206")
      (fields (field (name "LCSC PART #") "C17888") (field (name "Comment") "1206W4F0000T5E"))
      (libsource (lib "JLC_PCB") (part "1206W4F0000T5E"))
    )
    (comp (ref "R137")
      (value "0R")
      (footprint "R_1206")
      (description "R - RESISTOR - SMD - 0R - 1% - 1206")
      (fields (field (name "LCSC PART #") "C17888") (field (name "Comment") "1206W4F0000T5E"))
      (libsource (lib "JLC_PCB") (part "1206W4F0000T5E"))
    )
    (comp (ref "R138")
      (value "0R")
      (footprint "R_1206")
      (description "R - RESISTOR - SMD - 0R - 1% - 1206")
      (fields (field (name "LCSC PART #") "C17888") (field (name "Comment") "1206W4F0000T5E"))
      (libsource (lib "JLC_PCB") (part "1206W4F0000T5E"))
    )
  )
  (nets
    (net (code "1") (name "/primary") (class "Default")
      (node (ref "J1") (pin "1") (pinfunction "1_1") (pintype "passive"))
      (node (ref "J1") (pin "2") (pinfunction "2_2") (pintype "passive"))
      (node (ref "J1") (pin "3") (pinfunction "3_3") (pintype "passive"))
      (node (ref "J1") (pin "4") (pinfunction "4_4") (pintype "passive"))
      (node (ref "J1") (pin "5") (pinfunction "5_5") (pintype "passive"))
      (node (ref "J1") (pin "6") (pinfunction "6_6") (pintype "passive"))
      (node (ref "J1") (pin "7") (pinfunction "7_7") (pintype "passive"))
      (node (ref "J1") (pin "8") (pinfunction "8_8") (pintype "passive"))
      (node (ref "J2") (pin "1") (pinfunction "1_1") (pintype "passive"))
      (node (ref "J2") (pin "2") (pinfunction "2_2") (pintype "passive"))
      (node (ref "J2") (pin "3") (pinfunction "3_3") (pintype "passive"))
      (node (ref "J2") (pin "4") (pinfunction "4_4") (pintype "passive"))
      (node (ref "J2") (pin "5") (pinfunction "5_5") (pintype "passive"))
      (node (ref "J2") (pin "6") (pinfunction "6_6") (pintype "passive"))
      (node (ref "J2") (pin "7") (pinfunction "7_7") (pintype "passive"))
      (node (ref "J2") (pin "8") (pinfunction "8_8") (pintype "passive"))
      (node (ref "R1") (pin "1") (pinfunction "1_1") (pintype "passive"))
      (node (ref "R1") (pin "2") (pinfunction "2_2") (pintype "passive"))
      (node (ref "R10") (pin "1") (pinfunction "1_1") (pintype "passive"))
      (node (ref "R10") (pin "2") (pinfunction "2_2") (pintype "passive"))
      (node (ref "R100") (pin "1") (pinfunction "1_1") (pintype "passive"))
      (node (ref "R100") (pin "2") (pinfunction "2_2") (pintype "passive"))
      (node (ref "R101") (pin "1") (pinfunction "1_1") (pintype "passive"))
      (node (ref "R101") (pin "2") (pinfunction "2_2") (pintype "passive"))
      (node (ref "R102") (pin "1") (pinfunction "1_1") (pintype "passive"))
      (node (ref "R102") (pin "2") (pinfunction "2_2") (pintype "passive"))
      (node (ref "R103") (pin "1") (pinfunction "1_1") (pintype "passive"))
      (node (ref "R103") (pin "2") (pinfunction "2_2") (pintype "passive"))
      (node (ref "R104") (pin "1") (pinfunction "1_1") (pintype "passive"))
      (node (ref "R104") (pin "2") (pinfunction "2_2") (pintype "passive"))
      (node (ref "R105") (pin "1") (pinfunction "1_1") (pintype "passive"))
      (node (ref "R105") (pin "2") (pinfunction "2_2") (pintype "passive"))
      (node (ref "R106") (pin "1") (pinfunction "1_1") (pintype "passive"))
      (node (ref "R106") (pin "2") (pinfunction "2_2") (pintype "passive"))
      (node (ref "R107") (pin "1") (pinfunction "1_1") (pintype "passive"))
      (node (ref "R107") (pin "2") (pinfunction "2_2") (pintype "passive"))
      (node (ref "R108") (pin "1") (pinfunction "1_1") (pintype "passive"))
      (node (ref "R108") (pin "2") (pinfunction "2_2") (pintype "passive"))
      (node (ref "R109") (pin "1") (pinfunction "1_1") (pintype "passive"))
      (node (ref "R109") (pin "2") (pinfunction "2_2") (pintype "passive"))
      (node (ref "R11") (pin "1") (pinfunction "1_1") (pintype "passive"))
      (node (ref "R11") (pin "2") (pinfunction "2_2") (pintype "passive"))
      (node (ref "R110") (pin "1") (pinfunction "1_1") (pintype "passive"))
      (node (ref "R110") (pin "2") (pinfunction "2_2") (pintype "passive"))
      (node (ref "R111") (pin "1") (pinfunction "1_1") (pintype "passive"))
      (node (ref "R111") (pin "2") (pinfunction "2_2") (pintype "passive"))
      (node (ref "R112") (pin "1") (pinfunction "1_1") (pintype "passive"))
      (node (ref "R112") (pin "2") (pinfunction "2_2") (pintype "passive"))
      (node (ref "R113") (pin "1") (pinfunction "1_1") (pintype "passive"))
      (node (ref "R113") (pin "2") (pinfunction "2_2") (pintype "passive"))
      (node (ref "R114") (pin "1") (pinfunction "1_1") (pintype "passive"))
      (node (ref "R114") (pin "2") (pinfunction "2_2") (pintype "passive"))
      (node (ref "R115") (pin "1") (pinfunction "1_1") (pintype "passive"))
      (node (ref "R115") (pin "2") (pinfunction "2_2") (pintype "passive"))
      (node (ref "R116") (pin "1") (pinfunction "1_1") (pintype "passive"))
      (node (ref "R116") (pin "2") (pinfunction "2_2") (pintype "passive"))
      (node (ref "R117") (pin "1") (pinfunction "1_1") (pintype "passive"))
      (node (ref "R117") (pin "2") (pinfunction "2_2") (pintype "passive"))
      (node (ref "R118") (pin "1") (pinfunction "1_1") (pintype "passive"))
      (node (ref "R118") (pin "2") (pinfunction "2_2") (pintype "passive"))
      (node (ref "R119") (pin "1") (pinfunction "1_1") (pintype "passive"))
      (node (ref "R119") (pin "2") (pinfunction "2_2") (pintype "passive"))
      (node (ref "R12") (pin "1") (pinfunction "1_1") (pintype "passive"))
      (node (ref "R12") (pin "2") (pinfunction "2_2") (pintype "passive"))
      (node (ref "R120") (pin "1") (pinfunction "1_1") (pintype "passive"))
      (node (ref "R120") (pin "2") (pinfunction "2_2") (pintype "passive"))
      (node (ref "R121") (pin "1") (pinfunction "1_1") (pintype "passive"))
      (node (ref "R121") (pin "2") (pinfunction "2_2") (pintype "passive"))
      (node (ref "R122") (pin "1") (pinfunction "1_1") (pintype "passive"))
      (node (ref "R122") (pin "2") (pinfunction "2_2") (pintype "passive"))
      (node (ref "R123") (pin "1") (pinfunction "1_1") (pintype "passive"))
      (node (ref "R123") (pin "2") (pinfunction "2_2") (pintype "passive"))
      (node (ref "R127") (pin "1") (pinfunction "1_1") (pintype "passive"))
      (node (ref "R127") (pin "2") (pinfunction "2_2") (pintype "passive"))
      (node (ref "R128") (pin "1") (pinfunction "1_1") (pintype "passive"))
      (node (ref "R128") (pin "2") (pinfunction "2_2") (pintype "passive"))
      (node (ref "R129") (pin "1") (pinfunction "1_1") (pintype "passive"))
      (node (ref "R129") (pin "2") (pinfunction "2_2") (pintype "passive"))
      (node (ref "R13") (pin "1") (pinfunction "1_1") (pintype "passive"))
      (node (ref "R13") (pin "2") (pinfunction "2_2") (pintype "passive"))
      (node (ref "R130") (pin "1") (pinfunction "1_1") (pintype "passive"))
      (node (ref "R130") (pin "2") (pinfunction "2_2") (pintype "passive"))
      (node (ref "R131") (pin "1") (pinfunction "1_1") (pintype "passive"))
      (node (ref "R131") (pin "2") (pinfunction "2_2") (pintype "passive"))
      (node (ref "R132") (pin "1") (pinfunction "1_1") (pintype "passive"))
      (node (ref "R132") (pin "2") (pinfunction "2_2") (pintype "passive"))
      (node (ref "R133") (pin "1") (pinfunction "1_1") (pintype "passive"))
      (node (ref "R133") (pin "2") (pinfunction "2_2") (pintype "passive"))
      (node (ref "R134") (pin "1") (pinfunction "1_1") (pintype "passive"))
      (node (ref "R134") (pin "2") (pinfunction "2_2") (pintype "passive"))
      (node (ref "R136") (pin "1") (pinfunction "1_1") (pintype "passive"))
      (node (ref "R136") (pin "2") (pinfunction "2_2") (pintype "passive"))
      (node (ref "R137") (pin "1") (pinfunction "1_1") (pintype "passive"))
      (node (ref "R137") (pin "2") (pinfunction "2_2") (pintype "passive"))
      (node (ref "R138") (pin "1") (pinfunction "1_1") (pintype "passive"))
      (node (ref "R138") (pin "2") (pinfunction "2_2") (pintype "passive"))
      (node (ref "R14") (pin "1") (pinfunction "1_1") (pintype "passive"))
      (node (ref "R14") (pin "2") (pinfunction "2_2") (pintype "passive"))
      (node (ref "R15") (pin "1") (pinfunction "1_1") (pintype "passive"))
      (node (ref "R15") (pin "2") (pinfunction "2_2") (pintype "passive"))
      (node (ref "R16") (pin "1") (pinfunction "1_1") (pintype "passive"))
      (node (ref "R16") (pin "2") (pinfunction "2_2") (pintype "passive"))
      (node (ref "R17") (pin "1") (pinfunction "1_1") (pintype "passive"))
      (node (ref "R17") (pin "2") (pinfunction "2_2") (pintype "passive"))
      (node (ref "R18") (pin "1") (pinfunction "1_1") (pintype "passive"))
      (node (ref "R18") (pin "2") (pinfunction "2_2") (pintype "passive"))
      (node (ref "R19") (pin "1") (pinfunction "1_1") (pintype "passive"))
      (node (ref "R19") (pin "2") (pinfunction "2_2") (pintype "passive"))
      (node (ref "R2") (pin "1") (pinfunction "1_1") (pintype "passive"))
      (node (ref "R2") (pin "2") (pinfunction "2_2") (pintype "passive"))
      (node (ref "R20") (pin "1") (pinfunction "1_1") (pintype "passive"))
      (node (ref "R20") (pin "2") (pinfunction "2_2") (pintype "passive"))
      (node (ref "R21") (pin "1") (pinfunction "1_1") (pintype "passive"))
      (node (ref "R21") (pin "2") (pinfunction "2_2") (pintype "passive"))
      (node (ref "R22") (pin "1") (pinfunction "1_1") (pintype "passive"))
      (node (ref "R22") (pin "2") (pinfunction "2_2") (pintype "passive"))
      (node (ref "R23") (pin "1") (pinfunction "1_1") (pintype "passive"))
      (node (ref "R23") (pin "2") (pinfunction "2_2") (pintype "passive"))
      (node (ref "R24") (pin "1") (pinfunction "1_1") (pintype "passive"))
      (node (ref "R24") (pin "2") (pinfunction "2_2") (pintype "passive"))
      (node (ref "R25") (pin "1") (pinfunction "1_1") (pintype "passive"))
      (node (ref "R25") (pin "2") (pinfunction "2_2") (pintype "passive"))
      (node (ref "R26") (pin "1") (pinfunction "1_1") (pintype "passive"))
      (node (ref "R26") (pin "2") (pinfunction "2_2") (pintype "passive"))
      (node (ref "R27") (pin "1") (pinfunction "1_1") (pintype "passive"))
      (node (ref "R27") (pin "2") (pinfunction "2_2") (pintype "passive"))
      (node (ref "R28") (pin "1") (pinfunction "1_1") (pintype "passive"))
      (node (ref "R28") (pin "2") (pinfunction "2_2") (pintype "passive"))
      (node (ref "R29") (pin "1") (pinfunction "1_1") (pintype "passive"))
      (node (ref "R29") (pin "2") (pinfunction "2_2") (pintype "passive"))
      (node (ref "R3") (pin "1") (pinfunction "1_1") (pintype "passive"))
      (node (ref "R3") (pin "2") (pinfunction "2_2") (pintype "passive"))
      (node (ref "R30") (pin "1") (pinfunction "1_1") (pintype "passive"))
      (node (ref "R30") (pin "2") (pinfunction "2_2") (pintype "passive"))
      (node (ref "R31") (pin "1") (pinfunction "1_1") (pintype "passive"))
      (node (ref "R31") (pin "2") (pinfunction "2_2") (pintype "passive"))
      (node (ref "R32") (pin "1") (pinfunction "1_1") (pintype "passive"))
      (node (ref "R32") (pin "2") (pinfunction "2_2") (pintype "passive"))
      (node (ref "R33") (pin "1") (pinfunction "1_1") (pintype "passive"))
      (node (ref "R33") (pin "2") (pinfunction "2_2") (pintype "passive"))
      (node (ref "R34") (pin "1") (pinfunction "1_1") (pintype "passive"))
      (node (ref "R34") (pin "2") (pinfunction "2_2") (pintype "passive"))
      (node (ref "R35") (pin "1") (pinfunction "1_1") (pintype "passive"))
      (node (ref "R35") (pin "2") (pinfunction "2_2") (pintype "passive"))
      (node (ref "R36") (pin "1") (pinfunction "1_1") (pintype "passive"))
      (node (ref "R36") (pin "2") (pinfunction "2_2") (pintype "passive"))
      (node (ref "R37") (pin "1") (pinfunction "1_1") (pintype "passive"))
      (node (ref "R37") (pin "2") (pinfunction "2_2") (pintype "passive"))
      (node (ref "R38") (pin "1") (pinfunction "1_1") (pintype "passive"))
      (node (ref "R38") (pin "2") (pinfunction "2_2") (pintype "passive"))
      (node (ref "R39") (pin "1") (pinfunction "1_1") (pintype "passive"))
      (node (ref "R39") (pin "2") (pinfunction "2_2") (pintype "passive"))
      (node (ref "R4") (pin "1") (pinfunction "1_1") (pintype "passive"))
      (node (ref "R4") (pin "2") (pinfunction "2_2") (pintype "passive"))
      (node (ref "R40") (pin "1") (pinfunction "1_1") (pintype "passive"))
      (node (ref "R40") (pin "2") (pinfunction "2_2") (pintype "passive"))
      (node (ref "R41") (pin "1") (pinfunction "1_1") (pintype "passive"))
      (node (ref "R41") (pin "2") (pinfunction "2_2") (pintype "passive"))
      (node (ref "R42") (pin "1") (pinfunction "1_1") (pintype "passive"))
      (node (ref "R42") (pin "2") (pinfunction "2_2") (pintype "passive"))
      (node (ref "R43") (pin "1") (pinfunction "1_1") (pintype "passive"))
      (node (ref "R43") (pin "2") (pinfunction "2_2") (pintype "passive"))
      (node (ref "R44") (pin "1") (pinfunction "1_1") (pintype "passive"))
      (node (ref "R44") (pin "2") (pinfunction "2_2") (pintype "passive"))
      (node (ref "R45") (pin "1") (pinfunction "1_1") (pintype "passive"))
      (node (ref "R45") (pin "2") (pinfunction "2_2") (pintype "passive"))
      (node (ref "R46") (pin "1") (pinfunction "1_1") (pintype "passive"))
      (node (ref "R46") (pin "2") (pinfunction "2_2") (pintype "passive"))
      (node (ref "R47") (pin "1") (pinfunction "1_1") (pintype "passive"))
      (node (ref "R47") (pin "2") (pinfunction "2_2") (pintype "passive"))
      (node (ref "R48") (pin "1") (pinfunction "1_1") (pintype "passive"))
      (node (ref "R48") (pin "2") (pinfunction "2_2") (pintype "passive"))
      (node (ref "R49") (pin "1") (pinfunction "1_1") (pintype "passive"))
      (node (ref "R49") (pin "2") (pinfunction "2_2") (pintype "passive"))
      (node (ref "R5") (pin "1") (pinfunction "1_1") (pintype "passive"))
      (node (ref "R5") (pin "2") (pinfunction "2_2") (pintype "passive"))
      (node (ref "R50") (pin "1") (pinfunction "1_1") (pintype "passive"))
      (node (ref "R50") (pin "2") (pinfunction "2_2") (pintype "passive"))
      (node (ref "R51") (pin "1") (pinfunction "1_1") (pintype "passive"))
      (node (ref "R51") (pin "2") (pinfunction "2_2") (pintype "passive"))
      (node (ref "R52") (pin "1") (pinfunction "1_1") (pintype "passive"))
      (node (ref "R52") (pin "2") (pinfunction "2_2") (pintype "passive"))
      (node (ref "R53") (pin "1") (pinfunction "1_1") (pintype "passive"))
      (node (ref "R53") (pin "2") (pinfunction "2_2") (pintype "passive"))
      (node (ref "R54") (pin "1") (pinfunction "1_1") (pintype "passive"))
      (node (ref "R54") (pin "2") (pinfunction "2_2") (pintype "passive"))
      (node (ref "R55") (pin "1") (pinfunction "1_1") (pintype "passive"))
      (node (ref "R55") (pin "2") (pinfunction "2_2") (pintype "passive"))
      (node (ref "R56") (pin "1") (pinfunction "1_1") (pintype "passive"))
      (node (ref "R56") (pin "2") (pinfunction "2_2") (pintype "passive"))
      (node (ref "R57") (pin "1") (pinfunction "1_1") (pintype "passive"))
      (node (ref "R57") (pin "2") (pinfunction "2_2") (pintype "passive"))
      (node (ref "R58") (pin "1") (pinfunction "1_1") (pintype "passive"))
      (node (ref "R58") (pin "2") (pinfunction "2_2") (pintype "passive"))
      (node (ref "R59") (pin "1") (pinfunction "1_1") (pintype "passive"))
      (node (ref "R59") (pin "2") (pinfunction "2_2") (pintype "passive"))
      (node (ref "R6") (pin "1") (pinfunction "1_1") (pintype "passive"))
      (node (ref "R6") (pin "2") (pinfunction "2_2") (pintype "passive"))
      (node (ref "R60") (pin "1") (pinfunction "1_1") (pintype "passive"))
      (node (ref "R60") (pin "2") (pinfunction "2_2") (pintype "passive"))
      (node (ref "R61") (pin "1") (pinfunction "1_1") (pintype "passive"))
      (node (ref "R61") (pin "2") (pinfunction "2_2") (pintype "passive"))
      (node (ref "R62") (pin "1") (pinfunction "1_1") (pintype "passive"))
      (node (ref "R62") (pin "2") (pinfunction "2_2") (pintype "passive"))
      (node (ref "R63") (pin "1") (pinfunction "1_1") (pintype "passive"))
      (node (ref "R63") (pin "2") (pinfunction "2_2") (pintype "passive"))
      (node (ref "R64") (pin "1") (pinfunction "1_1") (pintype "passive"))
      (node (ref "R64") (pin "2") (pinfunction "2_2") (pintype "passive"))
      (node (ref "R65") (pin "1") (pinfunction "1_1") (pintype "passive"))
      (node (ref "R65") (pin "2") (pinfunction "2_2") (pintype "passive"))
      (node (ref "R66") (pin "1") (pinfunction "1_1") (pintype "passive"))
      (node (ref "R66") (pin "2") (pinfunction "2_2") (pintype "passive"))
      (node (ref "R67") (pin "1") (pinfunction "1_1") (pintype "passive"))
      (node (ref "R67") (pin "2") (pinfunction "2_2") (pintype "passive"))
      (node (ref "R68") (pin "1") (pinfunction "1_1") (pintype "passive"))
      (node (ref "R68") (pin "2") (pinfunction "2_2") (pintype "passive"))
      (node (ref "R69") (pin "1") (pinfunction "1_1") (pintype "passive"))
      (node (ref "R69") (pin "2") (pinfunction "2_2") (pintype "passive"))
      (node (ref "R7") (pin "1") (pinfunction "1_1") (pintype "passive"))
      (node (ref "R7") (pin "2") (pinfunction "2_2") (pintype "passive"))
      (node (ref "R70") (pin "1") (pinfunction "1_1") (pintype "passive"))
      (node (ref "R70") (pin "2") (pinfunction "2_2") (pintype "passive"))
      (node (ref "R71") (pin "1") (pinfunction "1_1") (pintype "passive"))
      (node (ref "R71") (pin "2") (pinfunction "2_2") (pintype "passive"))
      (node (ref "R72") (pin "1") (pinfunction "1_1") (pintype "passive"))
      (node (ref "R72") (pin "2") (pinfunction "2_2") (pintype "passive"))
      (node (ref "R73") (pin "1") (pinfunction "1_1") (pintype "passive"))
      (node (ref "R73") (pin "2") (pinfunction "2_2") (pintype "passive"))
      (node (ref "R74") (pin "1") (pinfunction "1_1") (pintype "passive"))
      (node (ref "R74") (pin "2") (pinfunction "2_2") (pintype "passive"))
      (node (ref "R75") (pin "1") (pinfunction "1_1") (pintype "passive"))
      (node (ref "R75") (pin "2") (pinfunction "2_2") (pintype "passive"))
      (node (ref "R76") (pin "1") (pinfunction "1_1") (pintype "passive"))
      (node (ref "R76") (pin "2") (pinfunction "2_2") (pintype "passive"))
      (node (ref "R77") (pin "1") (pinfunction "1_1") (pintype "passive"))
      (node (ref "R77") (pin "2") (pinfunction "2_2") (pintype "passive"))
      (node (ref "R78") (pin "1") (pinfunction "1_1") (pintype "passive"))
      (node (ref "R78") (pin "2") (pinfunction "2_2") (pintype "passive"))
      (node (ref "R79") (pin "1") (pinfunction "1_1") (pintype "passive"))
      (node (ref "R79") (pin "2") (pinfunction "2_2") (pintype "passive"))
      (node (ref "R8") (pin "1") (pinfunction "1_1") (pintype "passive"))
      (node (ref "R8") (pin "2") (pinfunction "2_2") (pintype "passive"))
      (node (ref "R80") (pin "1") (pinfunction "1_1") (pintype "passive"))
      (node (ref "R80") (pin "2") (pinfunction "2_2") (pintype "passive"))
      (node (ref "R81") (pin "1") (pinfunction "1_1") (pintype "passive"))
      (node (ref "R81") (pin "2") (pinfunction "2_2") (pintype "passive"))
      (node (ref "R82") (pin "1") (pinfunction "1_1") (pintype "passive"))
      (node (ref "R82") (pin "2") (pinfunction "2_2") (pintype "passive"))
      (node (ref "R83") (pin "1") (pinfunction "1_1") (pintype "passive"))
      (node (ref "R83") (pin "2") (pinfunction "2_2") (pintype "passive"))
      (node (ref "R84") (pin "1") (pinfunction "1_1") (pintype "passive"))
      (node (ref "R84") (pin "2") (pinfunction "2_2") (pintype "passive"))
      (node (ref "R85") (pin "1") (pinfunction "1_1") (pintype "passive"))
      (node (ref "R85") (pin "2") (pinfunction "2_2") (pintype "passive"))
      (node (ref "R86") (pin "1") (pinfunction "1_1") (pintype "passive"))
      (node (ref "R86") (pin "2") (pinfunction "2_2") (pintype "passive"))
      (node (ref "R87") (pin "1") (pinfunction "1_1") (pintype "passive"))
      (node (ref "R87") (pin "2") (pinfunction "2_2") (pintype "passive"))
      (node (ref "R88") (pin "1") (pinfunction "1_1") (pintype "passive"))
      (node (ref "R88") (pin "2") (pinfunction "2_2") (pintype "passive"))
      (node (ref "R89") (pin "1") (pinfunction "1_1") (pintype "passive"))
      (node (ref "R89") (pin "2") (pinfunction "2_2") (pintype "passive"))
      (node (ref "R9") (pin "1") (pinfunction "1_1") (pintype "passive"))
      (node (ref "R9") (pin "2") (pinfunction "2_2") (pintype "passive"))
      (node (ref "R90") (pin "1") (pinfunction "1_1") (pintype "passive"))
      (node (ref "R90") (pin "2") (pinfunction "2_2") (pintype "passive"))
      (node (ref "R91") (pin "1") (pinfunction "1_1") (pintype "passive"))
      (node (ref "R91") (pin "2") (pinfunction "2_2") (pintype "passive"))
      (node (ref "R92") (pin "1") (pinfunction "1_1") (pintype "passive"))
      (node (ref "R92") (pin "2") (pinfunction "2_2") (pintype "passive"))
      (node (ref "R93") (pin "1") (pinfunction "1_1") (pintype "passive"))
      (node (ref "R93") (pin "2") (pinfunction "2_2") (pintype "passive"))
      (node (ref "R94") (pin "1") (pinfunction "1_1") (pintype "passive"))
      (node (ref "R94") (pin "2") (pinfunction "2_2") (pintype "passive"))
      (node (ref "R95") (pin "1") (pinfunction "1_1") (pintype "passive"))
      (node (ref "R95") (pin "2") (pinfunction "2_2") (pintype "passive"))
      (node (ref "R96") (pin "1") (pinfunction "1_1") (pintype "passive"))
      (node (ref "R96") (pin "2") (pinfunction "2_2") (pintype "passive"))
      (node (ref "R97") (pin "1") (pinfunction "1_1") (pintype "passive"))
      (node (ref "R97") (pin "2") (pinfunction "2_2") (pintype "passive"))
      (node (ref "R98") (pin "1") (pinfunction "1_1") (pintype "passive"))
      (node (ref "R98") (pin "2") (pinfunction "2_2") (pintype "passive"))
      (node (ref "R99") (pin "1") (pinfunction "1_1") (pintype "passive"))
      (node (ref "R99") (pin "2") (pinfunction "2_2") (pintype "passive"))
    )
  )
)
